# item_2022_analog_02.net
KiCad netlist of a schematic drawn in EAGLE
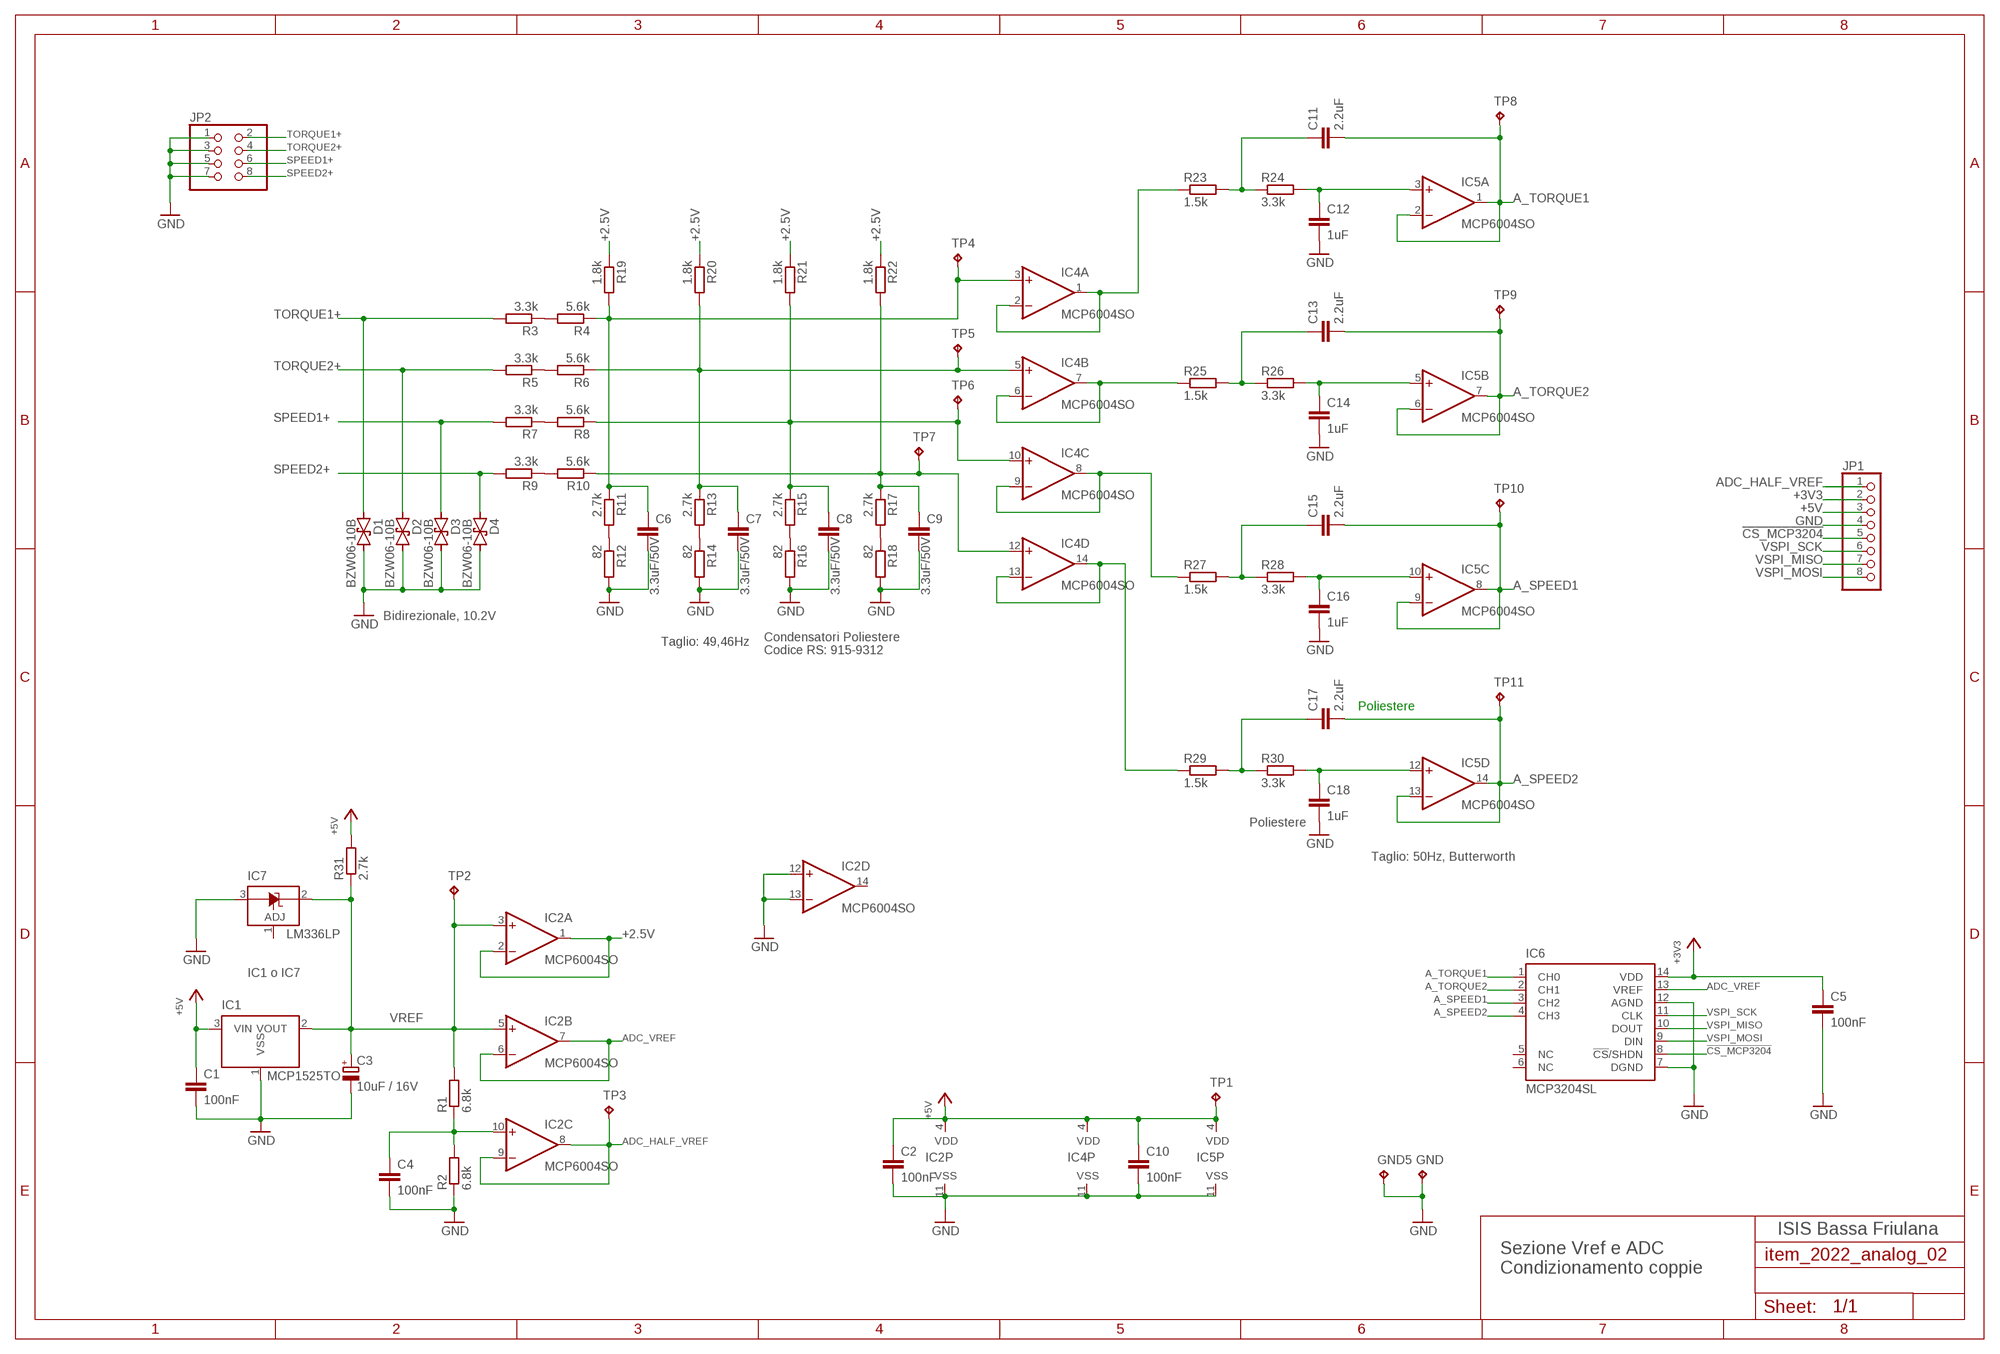
[diagram p0: schematic, sheet 1]

(export (version "E")
  (design (tool "Eeschema 10.0.6"))
  (components
    (comp (ref "C1")
      (value "100nF")
      (footprint "eagle-import:C0805")
      (libsource (lib "eagle-import") (part "C-EUC0805"))
    )
    (comp (ref "C2")
      (value "100nF")
      (footprint "eagle-import:C0805")
      (libsource (lib "eagle-import") (part "C-EUC0805"))
    )
    (comp (ref "C3")
      (value "10uF / 16V")
      (footprint "eagle-import:PANASONIC_C")
      (libsource (lib "eagle-import") (part "CPOL-EUC"))
    )
    (comp (ref "C4")
      (value "100nF")
      (footprint "eagle-import:C0805")
      (libsource (lib "eagle-import") (part "C-EUC0805"))
    )
    (comp (ref "C5")
      (value "100nF")
      (footprint "eagle-import:C0805")
      (libsource (lib "eagle-import") (part "C-EUC0805"))
    )
    (comp (ref "C6")
      (value "3.3uF/50V")
      (footprint "eagle-import:C0805")
      (libsource (lib "eagle-import") (part "C-EUC0805"))
    )
    (comp (ref "C7")
      (value "3.3uF/50V")
      (footprint "eagle-import:C0805")
      (libsource (lib "eagle-import") (part "C-EUC0805"))
    )
    (comp (ref "C8")
      (value "3.3uF/50V")
      (footprint "eagle-import:C0805")
      (libsource (lib "eagle-import") (part "C-EUC0805"))
    )
    (comp (ref "C9")
      (value "3.3uF/50V")
      (footprint "eagle-import:C0805")
      (libsource (lib "eagle-import") (part "C-EUC0805"))
    )
    (comp (ref "C10")
      (value "100nF")
      (footprint "eagle-import:C0805")
      (libsource (lib "eagle-import") (part "C-EUC0805"))
    )
    (comp (ref "C11")
      (value "2.2uF")
      (footprint "eagle-import:C0805")
      (libsource (lib "eagle-import") (part "C-EUC0805"))
    )
    (comp (ref "C12")
      (value "1uF")
      (footprint "eagle-import:C0805")
      (libsource (lib "eagle-import") (part "C-EUC0805"))
    )
    (comp (ref "C13")
      (value "2.2uF")
      (footprint "eagle-import:C0805")
      (libsource (lib "eagle-import") (part "C-EUC0805"))
    )
    (comp (ref "C14")
      (value "1uF")
      (footprint "eagle-import:C0805")
      (libsource (lib "eagle-import") (part "C-EUC0805"))
    )
    (comp (ref "C15")
      (value "2.2uF")
      (footprint "eagle-import:C0805")
      (libsource (lib "eagle-import") (part "C-EUC0805"))
    )
    (comp (ref "C16")
      (value "1uF")
      (footprint "eagle-import:C0805")
      (libsource (lib "eagle-import") (part "C-EUC0805"))
    )
    (comp (ref "C17")
      (value "2.2uF")
      (footprint "eagle-import:C0805")
      (libsource (lib "eagle-import") (part "C-EUC0805"))
    )
    (comp (ref "C18")
      (value "1uF")
      (footprint "eagle-import:C0805")
      (libsource (lib "eagle-import") (part "C-EUC0805"))
    )
    (comp (ref "D1")
      (value "BZW06-10B")
      (footprint "eagle-import:F126Z12")
      (libsource (lib "eagle-import") (part "BZW04XXB"))
    )
    (comp (ref "D2")
      (value "BZW06-10B")
      (footprint "eagle-import:F126Z12")
      (libsource (lib "eagle-import") (part "BZW04XXB"))
    )
    (comp (ref "D3")
      (value "BZW06-10B")
      (footprint "eagle-import:F126Z12")
      (libsource (lib "eagle-import") (part "BZW04XXB"))
    )
    (comp (ref "D4")
      (value "BZW06-10B")
      (footprint "eagle-import:F126Z12")
      (libsource (lib "eagle-import") (part "BZW04XXB"))
    )
    (comp (ref "GND")
      (value "TPTP18SQ")
      (footprint "eagle-import:TP18SQ")
      (libsource (lib "eagle-import") (part "TPTP18SQ"))
    )
    (comp (ref "GND5")
      (value "TPTP18SQ")
      (footprint "eagle-import:TP18SQ")
      (libsource (lib "eagle-import") (part "TPTP18SQ"))
    )
    (comp (ref "IC1")
      (value "MCP1525TO")
      (footprint "eagle-import:TO92")
      (libsource (lib "eagle-import") (part "MCP1525TO"))
    )
    (comp (ref "IC2")
      (value "MCP6004SO")
      (footprint "eagle-import:SO14")
      (libsource (lib "eagle-import") (part "MCP6004SO"))
    )
    (comp (ref "IC4")
      (value "MCP6004SO")
      (footprint "eagle-import:SO14")
      (libsource (lib "eagle-import") (part "MCP6004SO"))
    )
    (comp (ref "IC5")
      (value "MCP6004SO")
      (footprint "eagle-import:SO14")
      (libsource (lib "eagle-import") (part "MCP6004SO"))
    )
    (comp (ref "IC6")
      (value "MCP3204SL")
      (footprint "eagle-import:SO14")
      (libsource (lib "eagle-import") (part "MCP3204SL"))
    )
    (comp (ref "IC7")
      (value "LM336LP")
      (footprint "eagle-import:TO92")
      (libsource (lib "eagle-import") (part "LM336LP"))
    )
    (comp (ref "JP1")
      (value "PINHD-1X8")
      (footprint "eagle-import:1X08")
      (libsource (lib "eagle-import") (part "PINHD-1X8"))
    )
    (comp (ref "JP2")
      (value "PINHD-2X4")
      (footprint "eagle-import:2X04")
      (libsource (lib "eagle-import") (part "PINHD-2X4"))
    )
    (comp (ref "R1")
      (value "6.8k")
      (footprint "eagle-import:R0805")
      (libsource (lib "eagle-import") (part "rcl_LargePads_R-EU_R0805"))
    )
    (comp (ref "R2")
      (value "6.8k")
      (footprint "eagle-import:R0805")
      (libsource (lib "eagle-import") (part "rcl_LargePads_R-EU_R0805"))
    )
    (comp (ref "R3")
      (value "3.3k")
      (footprint "eagle-import:R0805")
      (libsource (lib "eagle-import") (part "rcl_LargePads_R-EU_R0805"))
    )
    (comp (ref "R4")
      (value "5.6k")
      (footprint "eagle-import:R0805")
      (libsource (lib "eagle-import") (part "rcl_LargePads_R-EU_R0805"))
    )
    (comp (ref "R5")
      (value "3.3k")
      (footprint "eagle-import:R0805")
      (libsource (lib "eagle-import") (part "rcl_LargePads_R-EU_R0805"))
    )
    (comp (ref "R6")
      (value "5.6k")
      (footprint "eagle-import:R0805")
      (libsource (lib "eagle-import") (part "rcl_LargePads_R-EU_R0805"))
    )
    (comp (ref "R7")
      (value "3.3k")
      (footprint "eagle-import:M0805")
      (libsource (lib "eagle-import") (part "rcl_LargePads_R-EU_M0805"))
    )
    (comp (ref "R8")
      (value "5.6k")
      (footprint "eagle-import:R0805")
      (libsource (lib "eagle-import") (part "rcl_LargePads_R-EU_R0805"))
    )
    (comp (ref "R9")
      (value "3.3k")
      (footprint "eagle-import:R0805")
      (libsource (lib "eagle-import") (part "rcl_LargePads_R-EU_R0805"))
    )
    (comp (ref "R10")
      (value "5.6k")
      (footprint "eagle-import:R0805")
      (libsource (lib "eagle-import") (part "rcl_LargePads_R-EU_R0805"))
    )
    (comp (ref "R11")
      (value "2.7k")
      (footprint "eagle-import:R0805")
      (libsource (lib "eagle-import") (part "rcl_LargePads_R-EU_R0805"))
    )
    (comp (ref "R12")
      (value "82")
      (footprint "eagle-import:R0805")
      (libsource (lib "eagle-import") (part "rcl_LargePads_R-EU_R0805"))
    )
    (comp (ref "R13")
      (value "2.7k")
      (footprint "eagle-import:R0805")
      (libsource (lib "eagle-import") (part "rcl_LargePads_R-EU_R0805"))
    )
    (comp (ref "R14")
      (value "82")
      (footprint "eagle-import:R0805")
      (libsource (lib "eagle-import") (part "rcl_LargePads_R-EU_R0805"))
    )
    (comp (ref "R15")
      (value "2.7k")
      (footprint "eagle-import:R0805")
      (libsource (lib "eagle-import") (part "rcl_LargePads_R-EU_R0805"))
    )
    (comp (ref "R16")
      (value "82")
      (footprint "eagle-import:R0805")
      (libsource (lib "eagle-import") (part "rcl_LargePads_R-EU_R0805"))
    )
    (comp (ref "R17")
      (value "2.7k")
      (footprint "eagle-import:R0805")
      (libsource (lib "eagle-import") (part "rcl_LargePads_R-EU_R0805"))
    )
    (comp (ref "R18")
      (value "82")
      (footprint "eagle-import:R0805")
      (libsource (lib "eagle-import") (part "rcl_LargePads_R-EU_R0805"))
    )
    (comp (ref "R19")
      (value "1.8k")
      (footprint "eagle-import:R0805")
      (libsource (lib "eagle-import") (part "rcl_LargePads_R-EU_R0805"))
    )
    (comp (ref "R20")
      (value "1.8k")
      (footprint "eagle-import:R0805")
      (libsource (lib "eagle-import") (part "rcl_LargePads_R-EU_R0805"))
    )
    (comp (ref "R21")
      (value "1.8k")
      (footprint "eagle-import:R0805")
      (libsource (lib "eagle-import") (part "rcl_LargePads_R-EU_R0805"))
    )
    (comp (ref "R22")
      (value "1.8k")
      (footprint "eagle-import:R0805")
      (libsource (lib "eagle-import") (part "rcl_LargePads_R-EU_R0805"))
    )
    (comp (ref "R23")
      (value "1.5k")
      (footprint "eagle-import:R0805")
      (libsource (lib "eagle-import") (part "rcl_LargePads_R-EU_R0805"))
    )
    (comp (ref "R24")
      (value "3.3k")
      (footprint "eagle-import:R0805")
      (libsource (lib "eagle-import") (part "rcl_LargePads_R-EU_R0805"))
    )
    (comp (ref "R25")
      (value "1.5k")
      (footprint "eagle-import:R0805")
      (libsource (lib "eagle-import") (part "rcl_LargePads_R-EU_R0805"))
    )
    (comp (ref "R26")
      (value "3.3k")
      (footprint "eagle-import:R0805")
      (libsource (lib "eagle-import") (part "rcl_LargePads_R-EU_R0805"))
    )
    (comp (ref "R27")
      (value "1.5k")
      (footprint "eagle-import:R0805")
      (libsource (lib "eagle-import") (part "rcl_LargePads_R-EU_R0805"))
    )
    (comp (ref "R28")
      (value "3.3k")
      (footprint "eagle-import:R0805")
      (libsource (lib "eagle-import") (part "rcl_LargePads_R-EU_R0805"))
    )
    (comp (ref "R29")
      (value "1.5k")
      (footprint "eagle-import:R0805")
      (libsource (lib "eagle-import") (part "rcl_LargePads_R-EU_R0805"))
    )
    (comp (ref "R30")
      (value "3.3k")
      (footprint "eagle-import:R0805")
      (libsource (lib "eagle-import") (part "rcl_LargePads_R-EU_R0805"))
    )
    (comp (ref "R31")
      (value "2.7k")
      (footprint "eagle-import:R0805")
      (libsource (lib "eagle-import") (part "R-EU_R0805"))
    )
    (comp (ref "TP1")
      (value "TPTP16R")
      (footprint "eagle-import:TP16R")
      (libsource (lib "eagle-import") (part "TPTP16R"))
    )
    (comp (ref "TP2")
      (value "TPTP16R")
      (footprint "eagle-import:TP16R")
      (libsource (lib "eagle-import") (part "TPTP16R"))
    )
    (comp (ref "TP3")
      (value "TPTP16R")
      (footprint "eagle-import:TP16R")
      (libsource (lib "eagle-import") (part "TPTP16R"))
    )
    (comp (ref "TP4")
      (value "TPTP14R")
      (footprint "eagle-import:TP14R")
      (libsource (lib "eagle-import") (part "TPTP14R"))
    )
    (comp (ref "TP5")
      (value "TPTP14R")
      (footprint "eagle-import:TP14R")
      (libsource (lib "eagle-import") (part "TPTP14R"))
    )
    (comp (ref "TP6")
      (value "TPTP14R")
      (footprint "eagle-import:TP14R")
      (libsource (lib "eagle-import") (part "TPTP14R"))
    )
    (comp (ref "TP7")
      (value "TPTP14R")
      (footprint "eagle-import:TP14R")
      (libsource (lib "eagle-import") (part "TPTP14R"))
    )
    (comp (ref "TP8")
      (value "TPTP14R")
      (footprint "eagle-import:TP14R")
      (libsource (lib "eagle-import") (part "TPTP14R"))
    )
    (comp (ref "TP9")
      (value "TPTP14R")
      (footprint "eagle-import:TP14R")
      (libsource (lib "eagle-import") (part "TPTP14R"))
    )
    (comp (ref "TP10")
      (value "TPTP14R")
      (footprint "eagle-import:TP14R")
      (libsource (lib "eagle-import") (part "TPTP14R"))
    )
    (comp (ref "TP11")
      (value "TPTP14R")
      (footprint "eagle-import:TP14R")
      (libsource (lib "eagle-import") (part "TPTP14R"))
    )
  )
  (nets
    (net (code "1") (name "+3V3") (class "Default")
      (node (ref "C5") (pin "1") (pinfunction "1_1") (pintype "passive"))
      (node (ref "IC6") (pin "14") (pinfunction "VDD_14") (pintype "power_in"))
      (node (ref "JP1") (pin "2") (pinfunction "2_2") (pintype "passive"))
    )
    (net (code "2") (name "+5V") (class "Default")
      (node (ref "C1") (pin "1") (pinfunction "1_1") (pintype "passive"))
      (node (ref "C10") (pin "1") (pinfunction "1_1") (pintype "passive"))
      (node (ref "C2") (pin "1") (pinfunction "1_1") (pintype "passive"))
      (node (ref "IC1") (pin "3") (pinfunction "VIN_3") (pintype "input"))
      (node (ref "IC2") (pin "4") (pinfunction "VDD_4") (pintype "power_in"))
      (node (ref "IC4") (pin "4") (pinfunction "VDD_4") (pintype "power_in"))
      (node (ref "IC5") (pin "4") (pinfunction "VDD_4") (pintype "power_in"))
      (node (ref "JP1") (pin "3") (pinfunction "3_3") (pintype "passive"))
      (node (ref "R31") (pin "2") (pinfunction "2_2") (pintype "passive"))
      (node (ref "TP1") (pin "TP") (pinfunction "TP_TP") (pintype "input"))
    )
    (net (code "3") (name "/+2.5V") (class "Default")
      (node (ref "IC2") (pin "1") (pinfunction "OUT_1") (pintype "output"))
      (node (ref "IC2") (pin "2") (pinfunction "-IN_2") (pintype "input"))
      (node (ref "R19") (pin "1") (pinfunction "1_1") (pintype "passive"))
      (node (ref "R20") (pin "1") (pinfunction "1_1") (pintype "passive"))
      (node (ref "R21") (pin "1") (pinfunction "1_1") (pintype "passive"))
      (node (ref "R22") (pin "1") (pinfunction "1_1") (pintype "passive"))
    )
    (net (code "4") (name "/ADC_HALF_VREF") (class "Default")
      (node (ref "IC2") (pin "8") (pinfunction "OUT_8") (pintype "output"))
      (node (ref "IC2") (pin "9") (pinfunction "-IN_9") (pintype "input"))
      (node (ref "JP1") (pin "1") (pinfunction "1_1") (pintype "passive"))
      (node (ref "TP3") (pin "TP") (pinfunction "TP_TP") (pintype "input"))
    )
    (net (code "5") (name "/ADC_VREF") (class "Default")
      (node (ref "IC2") (pin "6") (pinfunction "-IN_6") (pintype "input"))
      (node (ref "IC2") (pin "7") (pinfunction "OUT_7") (pintype "output"))
      (node (ref "IC6") (pin "13") (pinfunction "VREF_13") (pintype "power_in"))
    )
    (net (code "6") (name "/A_SPEED1") (class "Default")
      (node (ref "C15") (pin "2") (pinfunction "2_2") (pintype "passive"))
      (node (ref "IC5") (pin "8") (pinfunction "OUT_8") (pintype "output"))
      (node (ref "IC5") (pin "9") (pinfunction "-IN_9") (pintype "input"))
      (node (ref "IC6") (pin "3") (pinfunction "CH2_3") (pintype "input"))
      (node (ref "TP10") (pin "TP") (pinfunction "TP_TP") (pintype "input"))
    )
    (net (code "7") (name "/A_SPEED2") (class "Default")
      (node (ref "C17") (pin "2") (pinfunction "2_2") (pintype "passive"))
      (node (ref "IC5") (pin "13") (pinfunction "-IN_13") (pintype "input"))
      (node (ref "IC5") (pin "14") (pinfunction "OUT_14") (pintype "output"))
      (node (ref "IC6") (pin "4") (pinfunction "CH3_4") (pintype "input"))
      (node (ref "TP11") (pin "TP") (pinfunction "TP_TP") (pintype "input"))
    )
    (net (code "8") (name "/A_TORQUE1") (class "Default")
      (node (ref "C11") (pin "2") (pinfunction "2_2") (pintype "passive"))
      (node (ref "IC5") (pin "1") (pinfunction "OUT_1") (pintype "output"))
      (node (ref "IC5") (pin "2") (pinfunction "-IN_2") (pintype "input"))
      (node (ref "IC6") (pin "1") (pinfunction "CH0_1") (pintype "input"))
      (node (ref "TP8") (pin "TP") (pinfunction "TP_TP") (pintype "input"))
    )
    (net (code "9") (name "/A_TORQUE2") (class "Default")
      (node (ref "C13") (pin "2") (pinfunction "2_2") (pintype "passive"))
      (node (ref "IC5") (pin "6") (pinfunction "-IN_6") (pintype "input"))
      (node (ref "IC5") (pin "7") (pinfunction "OUT_7") (pintype "output"))
      (node (ref "IC6") (pin "2") (pinfunction "CH1_2") (pintype "input"))
      (node (ref "TP9") (pin "TP") (pinfunction "TP_TP") (pintype "input"))
    )
    (net (code "10") (name "/SPEED1+") (class "Default")
      (node (ref "D3") (pin "A") (pinfunction "1_A") (pintype "passive"))
      (node (ref "JP2") (pin "6") (pinfunction "6_6") (pintype "passive"))
      (node (ref "R7") (pin "2") (pinfunction "2_2") (pintype "passive"))
    )
    (net (code "11") (name "/SPEED2+") (class "Default")
      (node (ref "D4") (pin "A") (pinfunction "1_A") (pintype "passive"))
      (node (ref "JP2") (pin "8") (pinfunction "8_8") (pintype "passive"))
      (node (ref "R9") (pin "2") (pinfunction "2_2") (pintype "passive"))
    )
    (net (code "12") (name "/TORQUE1+") (class "Default")
      (node (ref "D1") (pin "A") (pinfunction "1_A") (pintype "passive"))
      (node (ref "JP2") (pin "2") (pinfunction "2_2") (pintype "passive"))
      (node (ref "R3") (pin "2") (pinfunction "2_2") (pintype "passive"))
    )
    (net (code "13") (name "/TORQUE2+") (class "Default")
      (node (ref "D2") (pin "A") (pinfunction "1_A") (pintype "passive"))
      (node (ref "JP2") (pin "4") (pinfunction "4_4") (pintype "passive"))
      (node (ref "R5") (pin "2") (pinfunction "2_2") (pintype "passive"))
    )
    (net (code "14") (name "/VREF") (class "Default")
      (node (ref "C3") (pin "+") (pinfunction "+_+") (pintype "passive"))
      (node (ref "IC1") (pin "2") (pinfunction "VOUT_2") (pintype "output"))
      (node (ref "IC2") (pin "3") (pinfunction "+IN_3") (pintype "input"))
      (node (ref "IC2") (pin "5") (pinfunction "+IN_5") (pintype "input"))
      (node (ref "IC7") (pin "2") (pinfunction "C_2") (pintype "passive"))
      (node (ref "R1") (pin "2") (pinfunction "2_2") (pintype "passive"))
      (node (ref "R31") (pin "1") (pinfunction "1_1") (pintype "passive"))
      (node (ref "TP2") (pin "TP") (pinfunction "TP_TP") (pintype "input"))
    )
    (net (code "15") (name "/VSPI_MISO") (class "Default")
      (node (ref "IC6") (pin "10") (pinfunction "DOUT_10") (pintype "input"))
      (node (ref "JP1") (pin "7") (pinfunction "7_7") (pintype "passive"))
    )
    (net (code "16") (name "/VSPI_MOSI") (class "Default")
      (node (ref "IC6") (pin "9") (pinfunction "DIN_9") (pintype "input"))
      (node (ref "JP1") (pin "8") (pinfunction "8_8") (pintype "passive"))
    )
    (net (code "17") (name "/VSPI_SCK") (class "Default")
      (node (ref "IC6") (pin "11") (pinfunction "CLK_11") (pintype "input"))
      (node (ref "JP1") (pin "6") (pinfunction "6_6") (pintype "passive"))
    )
    (net (code "18") (name "/~{CS_MCP3204}") (class "Default")
      (node (ref "IC6") (pin "8") (pinfunction "~{CS}/SHDN_8") (pintype "input"))
      (node (ref "JP1") (pin "5") (pinfunction "5_5") (pintype "passive"))
    )
    (net (code "19") (name "GND") (class "Default")
      (node (ref "C1") (pin "2") (pinfunction "2_2") (pintype "passive"))
      (node (ref "C10") (pin "2") (pinfunction "2_2") (pintype "passive"))
      (node (ref "C12") (pin "2") (pinfunction "2_2") (pintype "passive"))
      (node (ref "C14") (pin "2") (pinfunction "2_2") (pintype "passive"))
      (node (ref "C16") (pin "2") (pinfunction "2_2") (pintype "passive"))
      (node (ref "C18") (pin "2") (pinfunction "2_2") (pintype "passive"))
      (node (ref "C2") (pin "2") (pinfunction "2_2") (pintype "passive"))
      (node (ref "C3") (pin "-") (pinfunction "-_-") (pintype "passive"))
      (node (ref "C4") (pin "2") (pinfunction "2_2") (pintype "passive"))
      (node (ref "C5") (pin "2") (pinfunction "2_2") (pintype "passive"))
      (node (ref "C6") (pin "2") (pinfunction "2_2") (pintype "passive"))
      (node (ref "C7") (pin "2") (pinfunction "2_2") (pintype "passive"))
      (node (ref "C8") (pin "2") (pinfunction "2_2") (pintype "passive"))
      (node (ref "C9") (pin "2") (pinfunction "2_2") (pintype "passive"))
      (node (ref "D1") (pin "C") (pinfunction "2_C") (pintype "passive"))
      (node (ref "D2") (pin "C") (pinfunction "2_C") (pintype "passive"))
      (node (ref "D3") (pin "C") (pinfunction "2_C") (pintype "passive"))
      (node (ref "D4") (pin "C") (pinfunction "2_C") (pintype "passive"))
      (node (ref "GND") (pin "TP") (pinfunction "TP_TP") (pintype "input"))
      (node (ref "GND5") (pin "TP") (pinfunction "TP_TP") (pintype "input"))
      (node (ref "IC1") (pin "1") (pinfunction "VSS_1") (pintype "power_in"))
      (node (ref "IC2") (pin "11") (pinfunction "VSS_11") (pintype "power_in"))
      (node (ref "IC2") (pin "12") (pinfunction "+IN_12") (pintype "input"))
      (node (ref "IC2") (pin "13") (pinfunction "-IN_13") (pintype "input"))
      (node (ref "IC4") (pin "11") (pinfunction "VSS_11") (pintype "power_in"))
      (node (ref "IC5") (pin "11") (pinfunction "VSS_11") (pintype "power_in"))
      (node (ref "IC6") (pin "12") (pinfunction "AGND_12") (pintype "power_in"))
      (node (ref "IC6") (pin "7") (pinfunction "DGND_7") (pintype "power_in"))
      (node (ref "IC7") (pin "3") (pinfunction "A_3") (pintype "input"))
      (node (ref "JP1") (pin "4") (pinfunction "4_4") (pintype "passive"))
      (node (ref "JP2") (pin "1") (pinfunction "1_1") (pintype "passive"))
      (node (ref "JP2") (pin "3") (pinfunction "3_3") (pintype "passive"))
      (node (ref "JP2") (pin "5") (pinfunction "5_5") (pintype "passive"))
      (node (ref "JP2") (pin "7") (pinfunction "7_7") (pintype "passive"))
      (node (ref "R12") (pin "2") (pinfunction "2_2") (pintype "passive"))
      (node (ref "R14") (pin "2") (pinfunction "2_2") (pintype "passive"))
      (node (ref "R16") (pin "2") (pinfunction "2_2") (pintype "passive"))
      (node (ref "R18") (pin "2") (pinfunction "2_2") (pintype "passive"))
      (node (ref "R2") (pin "1") (pinfunction "1_1") (pintype "passive"))
    )
    (net (code "20") (name "Net-(C11-Pad1)") (class "Default")
      (node (ref "C11") (pin "1") (pinfunction "1_1") (pintype "passive"))
      (node (ref "R23") (pin "2") (pinfunction "2_2") (pintype "passive"))
      (node (ref "R24") (pin "1") (pinfunction "1_1") (pintype "passive"))
    )
    (net (code "21") (name "Net-(C13-Pad1)") (class "Default")
      (node (ref "C13") (pin "1") (pinfunction "1_1") (pintype "passive"))
      (node (ref "R25") (pin "2") (pinfunction "2_2") (pintype "passive"))
      (node (ref "R26") (pin "1") (pinfunction "1_1") (pintype "passive"))
    )
    (net (code "22") (name "Net-(C15-Pad1)") (class "Default")
      (node (ref "C15") (pin "1") (pinfunction "1_1") (pintype "passive"))
      (node (ref "R27") (pin "2") (pinfunction "2_2") (pintype "passive"))
      (node (ref "R28") (pin "1") (pinfunction "1_1") (pintype "passive"))
    )
    (net (code "23") (name "Net-(C17-Pad1)") (class "Default")
      (node (ref "C17") (pin "1") (pinfunction "1_1") (pintype "passive"))
      (node (ref "R29") (pin "2") (pinfunction "2_2") (pintype "passive"))
      (node (ref "R30") (pin "1") (pinfunction "1_1") (pintype "passive"))
    )
    (net (code "24") (name "Net-(IC2C-+IN)") (class "Default")
      (node (ref "C4") (pin "1") (pinfunction "1_1") (pintype "passive"))
      (node (ref "IC2") (pin "10") (pinfunction "+IN_10") (pintype "input"))
      (node (ref "R1") (pin "1") (pinfunction "1_1") (pintype "passive"))
      (node (ref "R2") (pin "2") (pinfunction "2_2") (pintype "passive"))
    )
    (net (code "25") (name "Net-(IC4A-+IN)") (class "Default")
      (node (ref "C6") (pin "1") (pinfunction "1_1") (pintype "passive"))
      (node (ref "IC4") (pin "3") (pinfunction "+IN_3") (pintype "input"))
      (node (ref "R11") (pin "1") (pinfunction "1_1") (pintype "passive"))
      (node (ref "R19") (pin "2") (pinfunction "2_2") (pintype "passive"))
      (node (ref "R4") (pin "1") (pinfunction "1_1") (pintype "passive"))
      (node (ref "TP4") (pin "TP") (pinfunction "TP_TP") (pintype "input"))
    )
    (net (code "26") (name "Net-(IC4A--IN)") (class "Default")
      (node (ref "IC4") (pin "1") (pinfunction "OUT_1") (pintype "output"))
      (node (ref "IC4") (pin "2") (pinfunction "-IN_2") (pintype "input"))
      (node (ref "R23") (pin "1") (pinfunction "1_1") (pintype "passive"))
    )
    (net (code "27") (name "Net-(IC4B-+IN)") (class "Default")
      (node (ref "C7") (pin "1") (pinfunction "1_1") (pintype "passive"))
      (node (ref "IC4") (pin "5") (pinfunction "+IN_5") (pintype "input"))
      (node (ref "R13") (pin "1") (pinfunction "1_1") (pintype "passive"))
      (node (ref "R20") (pin "2") (pinfunction "2_2") (pintype "passive"))
      (node (ref "R6") (pin "1") (pinfunction "1_1") (pintype "passive"))
      (node (ref "TP5") (pin "TP") (pinfunction "TP_TP") (pintype "input"))
    )
    (net (code "28") (name "Net-(IC4B--IN)") (class "Default")
      (node (ref "IC4") (pin "6") (pinfunction "-IN_6") (pintype "input"))
      (node (ref "IC4") (pin "7") (pinfunction "OUT_7") (pintype "output"))
      (node (ref "R25") (pin "1") (pinfunction "1_1") (pintype "passive"))
    )
    (net (code "29") (name "Net-(IC4C-+IN)") (class "Default")
      (node (ref "C8") (pin "1") (pinfunction "1_1") (pintype "passive"))
      (node (ref "IC4") (pin "10") (pinfunction "+IN_10") (pintype "input"))
      (node (ref "R15") (pin "1") (pinfunction "1_1") (pintype "passive"))
      (node (ref "R21") (pin "2") (pinfunction "2_2") (pintype "passive"))
      (node (ref "R8") (pin "1") (pinfunction "1_1") (pintype "passive"))
      (node (ref "TP6") (pin "TP") (pinfunction "TP_TP") (pintype "input"))
    )
    (net (code "30") (name "Net-(IC4C--IN)") (class "Default")
      (node (ref "IC4") (pin "8") (pinfunction "OUT_8") (pintype "output"))
      (node (ref "IC4") (pin "9") (pinfunction "-IN_9") (pintype "input"))
      (node (ref "R27") (pin "1") (pinfunction "1_1") (pintype "passive"))
    )
    (net (code "31") (name "Net-(IC4D-+IN)") (class "Default")
      (node (ref "C9") (pin "1") (pinfunction "1_1") (pintype "passive"))
      (node (ref "IC4") (pin "12") (pinfunction "+IN_12") (pintype "input"))
      (node (ref "R10") (pin "1") (pinfunction "1_1") (pintype "passive"))
      (node (ref "R17") (pin "1") (pinfunction "1_1") (pintype "passive"))
      (node (ref "R22") (pin "2") (pinfunction "2_2") (pintype "passive"))
      (node (ref "TP7") (pin "TP") (pinfunction "TP_TP") (pintype "input"))
    )
    (net (code "32") (name "Net-(IC4D--IN)") (class "Default")
      (node (ref "IC4") (pin "13") (pinfunction "-IN_13") (pintype "input"))
      (node (ref "IC4") (pin "14") (pinfunction "OUT_14") (pintype "output"))
      (node (ref "R29") (pin "1") (pinfunction "1_1") (pintype "passive"))
    )
    (net (code "33") (name "Net-(IC5A-+IN)") (class "Default")
      (node (ref "C12") (pin "1") (pinfunction "1_1") (pintype "passive"))
      (node (ref "IC5") (pin "3") (pinfunction "+IN_3") (pintype "input"))
      (node (ref "R24") (pin "2") (pinfunction "2_2") (pintype "passive"))
    )
    (net (code "34") (name "Net-(IC5B-+IN)") (class "Default")
      (node (ref "C14") (pin "1") (pinfunction "1_1") (pintype "passive"))
      (node (ref "IC5") (pin "5") (pinfunction "+IN_5") (pintype "input"))
      (node (ref "R26") (pin "2") (pinfunction "2_2") (pintype "passive"))
    )
    (net (code "35") (name "Net-(IC5C-+IN)") (class "Default")
      (node (ref "C16") (pin "1") (pinfunction "1_1") (pintype "passive"))
      (node (ref "IC5") (pin "10") (pinfunction "+IN_10") (pintype "input"))
      (node (ref "R28") (pin "2") (pinfunction "2_2") (pintype "passive"))
    )
    (net (code "36") (name "Net-(IC5D-+IN)") (class "Default")
      (node (ref "C18") (pin "1") (pinfunction "1_1") (pintype "passive"))
      (node (ref "IC5") (pin "12") (pinfunction "+IN_12") (pintype "input"))
      (node (ref "R30") (pin "2") (pinfunction "2_2") (pintype "passive"))
    )
    (net (code "37") (name "Net-(R3-Pad1)") (class "Default")
      (node (ref "R3") (pin "1") (pinfunction "1_1") (pintype "passive"))
      (node (ref "R4") (pin "2") (pinfunction "2_2") (pintype "passive"))
    )
    (net (code "38") (name "Net-(R5-Pad1)") (class "Default")
      (node (ref "R5") (pin "1") (pinfunction "1_1") (pintype "passive"))
      (node (ref "R6") (pin "2") (pinfunction "2_2") (pintype "passive"))
    )
    (net (code "39") (name "Net-(R7-Pad1)") (class "Default")
      (node (ref "R7") (pin "1") (pinfunction "1_1") (pintype "passive"))
      (node (ref "R8") (pin "2") (pinfunction "2_2") (pintype "passive"))
    )
    (net (code "40") (name "Net-(R10-Pad2)") (class "Default")
      (node (ref "R10") (pin "2") (pinfunction "2_2") (pintype "passive"))
      (node (ref "R9") (pin "1") (pinfunction "1_1") (pintype "passive"))
    )
    (net (code "41") (name "Net-(R11-Pad2)") (class "Default")
      (node (ref "R11") (pin "2") (pinfunction "2_2") (pintype "passive"))
      (node (ref "R12") (pin "1") (pinfunction "1_1") (pintype "passive"))
    )
    (net (code "42") (name "Net-(R13-Pad2)") (class "Default")
      (node (ref "R13") (pin "2") (pinfunction "2_2") (pintype "passive"))
      (node (ref "R14") (pin "1") (pinfunction "1_1") (pintype "passive"))
    )
    (net (code "43") (name "Net-(R15-Pad2)") (class "Default")
      (node (ref "R15") (pin "2") (pinfunction "2_2") (pintype "passive"))
      (node (ref "R16") (pin "1") (pinfunction "1_1") (pintype "passive"))
    )
    (net (code "44") (name "Net-(R17-Pad2)") (class "Default")
      (node (ref "R17") (pin "2") (pinfunction "2_2") (pintype "passive"))
      (node (ref "R18") (pin "1") (pinfunction "1_1") (pintype "passive"))
    )
    (net (code "45") (name "unconnected-(IC2D-OUT-Pad14)") (class "Default")
      (node (ref "IC2") (pin "14") (pinfunction "OUT_14") (pintype "output"))
    )
    (net (code "46") (name "unconnected-(IC6-NC-Pad5)") (class "Default")
      (node (ref "IC6") (pin "5") (pinfunction "NC_5") (pintype "no_connect"))
    )
    (net (code "47") (name "unconnected-(IC6-NC-Pad6)") (class "Default")
      (node (ref "IC6") (pin "6") (pinfunction "NC_6") (pintype "no_connect"))
    )
    (net (code "48") (name "unconnected-(IC7-ADJ-Pad1)") (class "Default")
      (node (ref "IC7") (pin "1") (pinfunction "ADJ_1") (pintype "input"))
    )
  )
)
